# design.net
KiCad netlist of a schematic drawn in Altium Designer
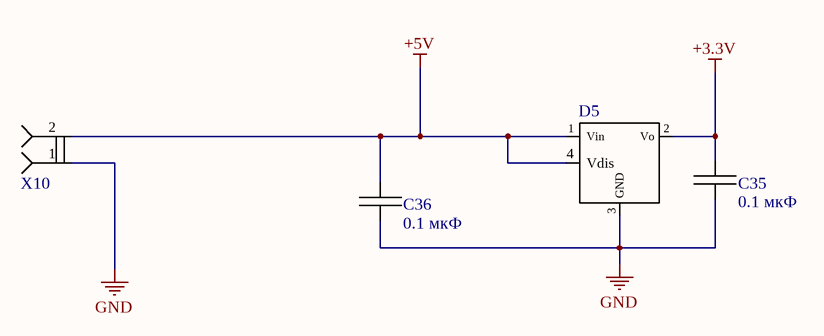
[diagram p0: Питание и сброс.SchDoc]

(export (version "E")
  (design (tool "Eeschema 10.0.6"))
  (components
    (comp (ref "C35")
      (value "0.1 мкФ")
      (footprint "К10-2,0х1,25х1,0")
      (fields
        (field (name "MANUFACTURER") "AVX")
        (field (name "MANUFACTURERPARTNUMBER") "0805ZD225KAT2A")
        (field (name "TOLERANCE") "±10%")
      )
      (libsource (lib "КОНДЕНСАТОРЫ") (part "0805-X5R-2,2мкФ-10В-10%"))
    )
    (comp (ref "C36")
      (value "0.1 мкФ")
      (footprint "К10-2,0х1,25х1,0")
      (fields
        (field (name "MANUFACTURER") "AVX")
        (field (name "MANUFACTURERPARTNUMBER") "0805ZD225KAT2A")
        (field (name "TOLERANCE") "±10%")
      )
      (libsource (lib "КОНДЕНСАТОРЫ") (part "0805-X5R-2,2мкФ-10В-10%"))
    )
    (comp (ref "D5")
      (value "~")
      (footprint "TO220-F-4L")
      (description "KA278R33")
      (fields (field (name "MANUFACTURERPARTNUMBER") "LM317MQDCYR"))
      (libsource (lib "МИКРОСХЕМЫ") (part "KA278R33"))
    )
    (comp (ref "X10")
      (value "~")
      (footprint "284392-2_TE")
      (fields
        (field (name "MANUFACTURER") "Tyco Electronics")
        (field (name "MANUFACTURERPARTNUMBER") "284392-2")
      )
      (libsource (lib "РАЗЪЕМЫ") (part "Клемник 3.81х2 TE"))
    )
  )
  (nets
    (net (code "1") (name "+3.3V") (class "Default")
      (node (ref "C35") (pin "2") (pinfunction "2_2") (pintype "passive"))
      (node (ref "D5") (pin "2") (pinfunction "Vo_2") (pintype "power_in"))
    )
    (net (code "2") (name "+5V") (class "Default")
      (node (ref "C36") (pin "2") (pinfunction "2_2") (pintype "passive"))
      (node (ref "D5") (pin "1") (pinfunction "Vin_1") (pintype "power_in"))
      (node (ref "D5") (pin "4") (pinfunction "Vdis_4") (pintype "passive"))
      (node (ref "X10") (pin "2") (pinfunction "2_2") (pintype "passive"))
    )
    (net (code "3") (name "GND") (class "Default")
      (node (ref "C35") (pin "1") (pinfunction "1_1") (pintype "passive"))
      (node (ref "C36") (pin "1") (pinfunction "1_1") (pintype "passive"))
      (node (ref "D5") (pin "3") (pinfunction "GND_3") (pintype "power_in"))
      (node (ref "X10") (pin "1") (pinfunction "1_1") (pintype "passive"))
    )
  )
)
